# RC_Reciever_SchDoc.net
KiCad netlist of a schematic drawn in Altium Designer
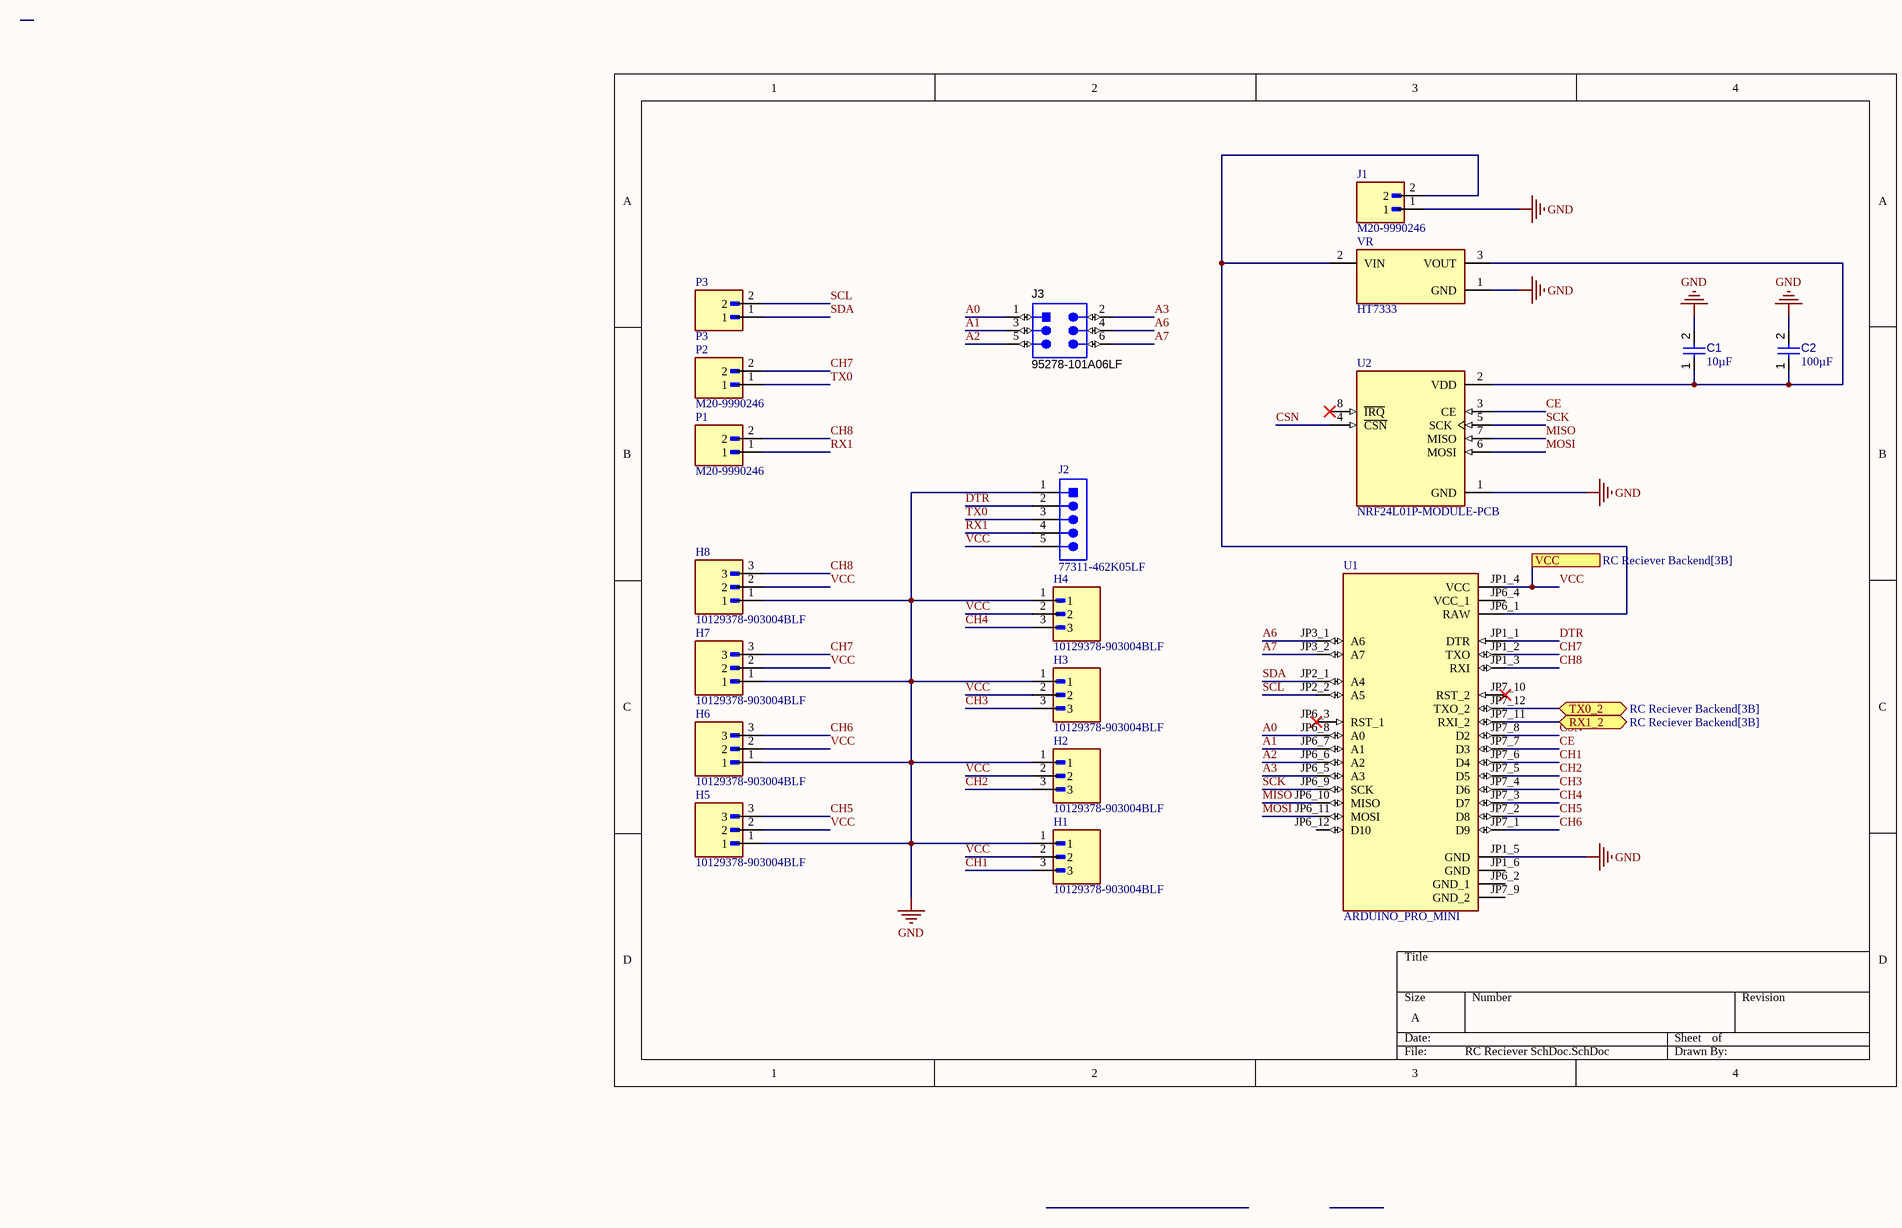
[diagram p0: RC Reciever SchDoc.SchDoc]

(export (version "E")
  (design (tool "Eeschema 10.0.6"))
  (components
    (comp (ref "C1")
      (value "10µF")
      (footprint "CAPC0603(1608)100_L")
      (description "Chip Capacitor, 10µF +/-20%, 10V, 0603, Thickness 1 mm")
      (fields (field (name "TOLERANCE") "10%") (field (name "Comment") "Capacitor 10µF +/-20% 10V 0603"))
      (libsource (lib "ishmail chowdhury") (part "CAP-NP-2"))
    )
    (comp (ref "C2")
      (value "100µF")
      (footprint "CAPC3216X190X55LL30T25")
      (description "Chip Capacitor, 100 uF, +/- 20%, 6.3 V, 1206 (3216 Metric)")
      (fields (field (name "TOLERANCE") "20%") (field (name "Comment") "Capacitor 100 uF +/- 20% 6.3 V 1206"))
      (libsource (lib "ishmail chowdhury") (part "CAP-NP-2"))
    )
    (comp (ref "H1")
      (value "10129378-903004BLF")
      (footprint "AMPHENOL_10129378-903004BLF")
      (fields (field (name "MF") "{'manufacturer': u'Amphenol ICC (FCI)'}"))
      (libsource (lib "10129378-903004BLF") (part "10129378-903004BLF"))
    )
    (comp (ref "H2")
      (value "10129378-903004BLF")
      (footprint "AMPHENOL_10129378-903004BLF")
      (fields (field (name "MF") "{'manufacturer': u'Amphenol ICC (FCI)'}"))
      (libsource (lib "10129378-903004BLF") (part "10129378-903004BLF"))
    )
    (comp (ref "H3")
      (value "10129378-903004BLF")
      (footprint "AMPHENOL_10129378-903004BLF")
      (fields (field (name "MF") "{'manufacturer': u'Amphenol ICC (FCI)'}"))
      (libsource (lib "10129378-903004BLF") (part "10129378-903004BLF"))
    )
    (comp (ref "H4")
      (value "10129378-903004BLF")
      (footprint "AMPHENOL_10129378-903004BLF")
      (fields (field (name "MF") "{'manufacturer': u'Amphenol ICC (FCI)'}"))
      (libsource (lib "10129378-903004BLF") (part "10129378-903004BLF"))
    )
    (comp (ref "H5")
      (value "10129378-903004BLF")
      (footprint "AMPHENOL_10129378-903004BLF")
      (fields (field (name "MF") "{'manufacturer': u'Amphenol ICC (FCI)'}"))
      (libsource (lib "") (part "10129378-903004BLF_1"))
    )
    (comp (ref "H6")
      (value "10129378-903004BLF")
      (footprint "AMPHENOL_10129378-903004BLF")
      (fields (field (name "MF") "{'manufacturer': u'Amphenol ICC (FCI)'}"))
      (libsource (lib "") (part "10129378-903004BLF_1"))
    )
    (comp (ref "H7")
      (value "10129378-903004BLF")
      (footprint "AMPHENOL_10129378-903004BLF")
      (fields (field (name "MF") "{'manufacturer': u'Amphenol ICC (FCI)'}"))
      (libsource (lib "") (part "10129378-903004BLF_1"))
    )
    (comp (ref "H8")
      (value "10129378-903004BLF")
      (footprint "AMPHENOL_10129378-903004BLF")
      (fields (field (name "MF") "{'manufacturer': u'Amphenol ICC (FCI)'}"))
      (libsource (lib "") (part "10129378-903004BLF_1"))
    )
    (comp (ref "J1")
      (value "M20-9990246")
      (footprint "HARWIN_M20-9990246")
      (description "2.54mm (0.1) Pitch SIL Vertical Throughboard Pin Header, 6.1mm mating pin height, tin, 2 contacts")
      (fields (field (name "MF") "Harwin"))
      (libsource (lib "M20-9990246") (part "M20-9990246"))
    )
    (comp (ref "J2")
      (value "77311-462K05LF")
      (footprint "FCI-77311-5_V")
      (fields (field (name "MANUFACTURER") "FCI Electronics"))
      (libsource (lib "ishmail chowdhury") (part "CN-1P-M-R5"))
    )
    (comp (ref "J3")
      (value "95278-101A06LF")
      (footprint "AMPM-95278-101A06LF_V")
      (description "Male Header, Pitch 2.54 mm, 2 x 3 Position, Height 14.4 mm, RoHS, Tape and Reel")
      (fields (field (name "MANUFACTURER") "Amphenol"))
      (libsource (lib "ishmail chowdhury") (part "CN-2P-M-R6"))
    )
    (comp (ref "P1")
      (value "M20-9990246")
      (footprint "HARWIN_M20-9990246")
      (description "2.54mm (0.1) Pitch SIL Vertical Throughboard Pin Header, 6.1mm mating pin height, tin, 2 contacts")
      (fields (field (name "MF") "Harwin"))
      (libsource (lib "M20-9990246") (part "M20-9990246"))
    )
    (comp (ref "P2")
      (value "M20-9990246")
      (footprint "HARWIN_M20-9990246")
      (description "2.54mm (0.1) Pitch SIL Vertical Throughboard Pin Header, 6.1mm mating pin height, tin, 2 contacts")
      (fields (field (name "MF") "Harwin"))
      (libsource (lib "M20-9990246") (part "M20-9990246"))
    )
    (comp (ref "P3")
      (value "P3")
      (footprint "HARWIN_M20-9990246")
      (description "2.54mm (0.1) Pitch SIL Vertical Throughboard Pin Header, 6.1mm mating pin height, tin, 2 contacts")
      (fields (field (name "MF") "Harwin") (field (name "MP") "M20-9990246"))
      (libsource (lib "M20-9990246") (part "M20-9990246"))
    )
    (comp (ref "U1")
      (value "ARDUINO_PRO_MINI")
      (footprint "MODULE_ARDUINO_PRO_MINI")
      (fields (field (name "MF") "Arduino") (field (name "MP") "Arduino Pro Mini"))
      (libsource (lib "ARDUINO_PRO_MINI") (part "ARDUINO_PRO_MINI"))
    )
    (comp (ref "U2")
      (value "NRF24L01P-MODULE-PCB")
      (footprint "XCVR_NRF24L01P-MODULE-PCB:XCVR_NRF24L01P-MODULE-PCB")
      (description "- Transceiver For Use With nRF24L01+")
      (fields (field (name "MF") "Nordic Semiconductor"))
      (libsource (lib "NRF24L01P-MODULE-PCB") (part "NRF24L01P-MODULE-PCB"))
    )
    (comp (ref "VR")
      (value "HT7333")
      (footprint "IC_HT7333")
      (description "Three-terminal, low power, high voltage regulator implemented in CMOS technology")
      (fields (field (name "MF") "Holtek Semiconductor"))
      (libsource (lib "HT7333") (part "HT7333"))
    )
  )
  (nets
    (net (code "1") (name "/A0") (class "Default")
      (node (ref "J3") (pin "1") (pinfunction "1_1") (pintype "bidirectional"))
      (node (ref "U1") (pin "JP6_8") (pinfunction "A0_JP6_8") (pintype "bidirectional"))
    )
    (net (code "2") (name "/A1") (class "Default")
      (node (ref "J3") (pin "3") (pinfunction "3_3") (pintype "bidirectional"))
      (node (ref "U1") (pin "JP6_7") (pinfunction "A1_JP6_7") (pintype "bidirectional"))
    )
    (net (code "3") (name "/A2") (class "Default")
      (node (ref "J3") (pin "5") (pinfunction "5_5") (pintype "bidirectional"))
      (node (ref "U1") (pin "JP6_6") (pinfunction "A2_JP6_6") (pintype "bidirectional"))
    )
    (net (code "4") (name "/A3") (class "Default")
      (node (ref "J3") (pin "2") (pinfunction "2_2") (pintype "bidirectional"))
      (node (ref "U1") (pin "JP6_5") (pinfunction "A3_JP6_5") (pintype "bidirectional"))
    )
    (net (code "5") (name "/A6") (class "Default")
      (node (ref "J3") (pin "4") (pinfunction "4_4") (pintype "bidirectional"))
      (node (ref "U1") (pin "JP3_1") (pinfunction "A6_JP3_1") (pintype "bidirectional"))
    )
    (net (code "6") (name "/A7") (class "Default")
      (node (ref "J3") (pin "6") (pinfunction "6_6") (pintype "bidirectional"))
      (node (ref "U1") (pin "JP3_2") (pinfunction "A7_JP3_2") (pintype "bidirectional"))
    )
    (net (code "7") (name "/CE") (class "Default")
      (node (ref "U1") (pin "JP7_7") (pinfunction "D3_JP7_7") (pintype "bidirectional"))
      (node (ref "U2") (pin "3") (pinfunction "CE_3") (pintype "input"))
    )
    (net (code "8") (name "/CH1") (class "Default")
      (node (ref "H1") (pin "3") (pinfunction "3_3") (pintype "passive"))
      (node (ref "U1") (pin "JP7_6") (pinfunction "D4_JP7_6") (pintype "bidirectional"))
    )
    (net (code "9") (name "/CH2") (class "Default")
      (node (ref "H2") (pin "3") (pinfunction "3_3") (pintype "passive"))
      (node (ref "U1") (pin "JP7_5") (pinfunction "D5_JP7_5") (pintype "bidirectional"))
    )
    (net (code "10") (name "/CH3") (class "Default")
      (node (ref "H3") (pin "3") (pinfunction "3_3") (pintype "passive"))
      (node (ref "U1") (pin "JP7_4") (pinfunction "D6_JP7_4") (pintype "bidirectional"))
    )
    (net (code "11") (name "/CH4") (class "Default")
      (node (ref "H4") (pin "3") (pinfunction "3_3") (pintype "passive"))
      (node (ref "U1") (pin "JP7_3") (pinfunction "D7_JP7_3") (pintype "bidirectional"))
    )
    (net (code "12") (name "/CH5") (class "Default")
      (node (ref "H5") (pin "3") (pinfunction "3_3") (pintype "passive"))
      (node (ref "U1") (pin "JP7_2") (pinfunction "D8_JP7_2") (pintype "bidirectional"))
    )
    (net (code "13") (name "/CH6") (class "Default")
      (node (ref "H6") (pin "3") (pinfunction "3_3") (pintype "passive"))
      (node (ref "U1") (pin "JP7_1") (pinfunction "D9_JP7_1") (pintype "bidirectional"))
    )
    (net (code "14") (name "/CH7") (class "Default")
      (node (ref "H7") (pin "3") (pinfunction "3_3") (pintype "passive"))
      (node (ref "P2") (pin "2") (pinfunction "2_2") (pintype "passive"))
      (node (ref "U1") (pin "JP1_2") (pinfunction "TXO_JP1_2") (pintype "bidirectional"))
    )
    (net (code "15") (name "/CH8") (class "Default")
      (node (ref "H8") (pin "3") (pinfunction "3_3") (pintype "passive"))
      (node (ref "P1") (pin "2") (pinfunction "2_2") (pintype "passive"))
      (node (ref "U1") (pin "JP1_3") (pinfunction "RXI_JP1_3") (pintype "bidirectional"))
    )
    (net (code "16") (name "/CSN") (class "Default")
      (node (ref "U1") (pin "JP7_8") (pinfunction "D2_JP7_8") (pintype "bidirectional"))
      (node (ref "U2") (pin "4") (pinfunction "~{CSN}_4") (pintype "input"))
    )
    (net (code "17") (name "/DTR") (class "Default")
      (node (ref "J2") (pin "2") (pinfunction "RXI_2") (pintype "passive"))
      (node (ref "U1") (pin "JP1_1") (pinfunction "DTR_JP1_1") (pintype "input"))
    )
    (net (code "18") (name "/MISO") (class "Default")
      (node (ref "U1") (pin "JP6_10") (pinfunction "MISO_JP6_10") (pintype "bidirectional"))
      (node (ref "U2") (pin "7") (pinfunction "MISO_7") (pintype "input"))
    )
    (net (code "19") (name "/MOSI") (class "Default")
      (node (ref "U1") (pin "JP6_11") (pinfunction "MOSI_JP6_11") (pintype "bidirectional"))
      (node (ref "U2") (pin "6") (pinfunction "MOSI_6") (pintype "input"))
    )
    (net (code "20") (name "/RX1") (class "Default")
      (node (ref "J2") (pin "4") (pinfunction "VCC_4") (pintype "passive"))
      (node (ref "P1") (pin "1") (pinfunction "1_1") (pintype "passive"))
    )
    (net (code "21") (name "/RX1_2") (class "Default")
      (node (ref "U1") (pin "JP7_11") (pinfunction "RXI_2_JP7_11") (pintype "bidirectional"))
    )
    (net (code "22") (name "/SCK") (class "Default")
      (node (ref "U1") (pin "JP6_9") (pinfunction "SCK_JP6_9") (pintype "bidirectional"))
      (node (ref "U2") (pin "5") (pinfunction "SCK_5") (pintype "input"))
    )
    (net (code "23") (name "/SCL") (class "Default")
      (node (ref "P3") (pin "2") (pinfunction "2_2") (pintype "passive"))
      (node (ref "U1") (pin "JP2_2") (pinfunction "A5_JP2_2") (pintype "bidirectional"))
    )
    (net (code "24") (name "/SDA") (class "Default")
      (node (ref "P3") (pin "1") (pinfunction "1_1") (pintype "passive"))
      (node (ref "U1") (pin "JP2_1") (pinfunction "A4_JP2_1") (pintype "bidirectional"))
    )
    (net (code "25") (name "/TX0") (class "Default")
      (node (ref "J2") (pin "3") (pinfunction "TXO_3") (pintype "passive"))
      (node (ref "P2") (pin "1") (pinfunction "1_1") (pintype "passive"))
    )
    (net (code "26") (name "/TX0_2") (class "Default")
      (node (ref "U1") (pin "JP7_12") (pinfunction "TXO_2_JP7_12") (pintype "bidirectional"))
    )
    (net (code "27") (name "/VCC") (class "Default")
      (node (ref "H1") (pin "2") (pinfunction "2_2") (pintype "passive"))
      (node (ref "H2") (pin "2") (pinfunction "2_2") (pintype "passive"))
      (node (ref "H3") (pin "2") (pinfunction "2_2") (pintype "passive"))
      (node (ref "H4") (pin "2") (pinfunction "2_2") (pintype "passive"))
      (node (ref "H5") (pin "2") (pinfunction "2_2") (pintype "passive"))
      (node (ref "H6") (pin "2") (pinfunction "2_2") (pintype "passive"))
      (node (ref "H7") (pin "2") (pinfunction "2_2") (pintype "passive"))
      (node (ref "H8") (pin "2") (pinfunction "2_2") (pintype "passive"))
      (node (ref "J2") (pin "5") (pinfunction "CTS_5") (pintype "passive"))
      (node (ref "U1") (pin "JP1_4") (pinfunction "VCC_JP1_4") (pintype "power_in"))
    )
    (net (code "28") (name "GND") (class "Default")
      (node (ref "C1") (pin "2") (pinfunction "2_2") (pintype "passive"))
      (node (ref "C2") (pin "2") (pinfunction "2_2") (pintype "passive"))
      (node (ref "H1") (pin "1") (pinfunction "1_1") (pintype "passive"))
      (node (ref "H2") (pin "1") (pinfunction "1_1") (pintype "passive"))
      (node (ref "H3") (pin "1") (pinfunction "1_1") (pintype "passive"))
      (node (ref "H4") (pin "1") (pinfunction "1_1") (pintype "passive"))
      (node (ref "H5") (pin "1") (pinfunction "1_1") (pintype "passive"))
      (node (ref "H6") (pin "1") (pinfunction "1_1") (pintype "passive"))
      (node (ref "H7") (pin "1") (pinfunction "1_1") (pintype "passive"))
      (node (ref "H8") (pin "1") (pinfunction "1_1") (pintype "passive"))
      (node (ref "J1") (pin "1") (pinfunction "1_1") (pintype "passive"))
      (node (ref "J2") (pin "1") (pinfunction "DTR_1") (pintype "passive"))
      (node (ref "U1") (pin "JP1_5") (pinfunction "GND_JP1_5") (pintype "power_in"))
      (node (ref "U2") (pin "1") (pinfunction "GND_1") (pintype "power_in"))
      (node (ref "VR") (pin "1") (pinfunction "GND_1") (pintype "power_in"))
    )
    (net (code "29") (name "Net-(U1-RAW)") (class "Default")
      (node (ref "J1") (pin "2") (pinfunction "2_2") (pintype "passive"))
      (node (ref "U1") (pin "JP6_1") (pinfunction "RAW_JP6_1") (pintype "power_in"))
      (node (ref "VR") (pin "2") (pinfunction "VIN_2") (pintype "power_in"))
    )
    (net (code "30") (name "Net-(U2-VDD)") (class "Default")
      (node (ref "C1") (pin "1") (pinfunction "1_1") (pintype "passive"))
      (node (ref "C2") (pin "1") (pinfunction "1_1") (pintype "passive"))
      (node (ref "U2") (pin "2") (pinfunction "VDD_2") (pintype "power_in"))
      (node (ref "VR") (pin "3") (pinfunction "VOUT_3") (pintype "power_in"))
    )
    (net (code "31") (name "unconnected-(U1-D10-PadJP6_12)") (class "Default")
      (node (ref "U1") (pin "JP6_12") (pinfunction "D10_JP6_12") (pintype "bidirectional"))
    )
    (net (code "32") (name "unconnected-(U1-GND-PadJP1_6)") (class "Default")
      (node (ref "U1") (pin "JP1_6") (pinfunction "GND_JP1_6") (pintype "power_in"))
    )
    (net (code "33") (name "unconnected-(U1-GND_1-PadJP6_2)") (class "Default")
      (node (ref "U1") (pin "JP6_2") (pinfunction "GND_1_JP6_2") (pintype "power_in"))
    )
    (net (code "34") (name "unconnected-(U1-GND_2-PadJP7_9)") (class "Default")
      (node (ref "U1") (pin "JP7_9") (pinfunction "GND_2_JP7_9") (pintype "power_in"))
    )
    (net (code "35") (name "unconnected-(U1-RST_1-PadJP6_3)") (class "Default")
      (node (ref "U1") (pin "JP6_3") (pinfunction "RST_1_JP6_3") (pintype "input+no_connect"))
    )
    (net (code "36") (name "unconnected-(U1-RST_2-PadJP7_10)") (class "Default")
      (node (ref "U1") (pin "JP7_10") (pinfunction "RST_2_JP7_10") (pintype "input+no_connect"))
    )
    (net (code "37") (name "unconnected-(U1-VCC_1-PadJP6_4)") (class "Default")
      (node (ref "U1") (pin "JP6_4") (pinfunction "VCC_1_JP6_4") (pintype "power_in"))
    )
    (net (code "38") (name "unconnected-(U2-~{IRQ}-Pad8)") (class "Default")
      (node (ref "U2") (pin "8") (pinfunction "~{IRQ}_8") (pintype "input+no_connect"))
    )
  )
)
